# CentralUnit_Schematic.net
KiCad netlist of a schematic drawn in Altium Designer
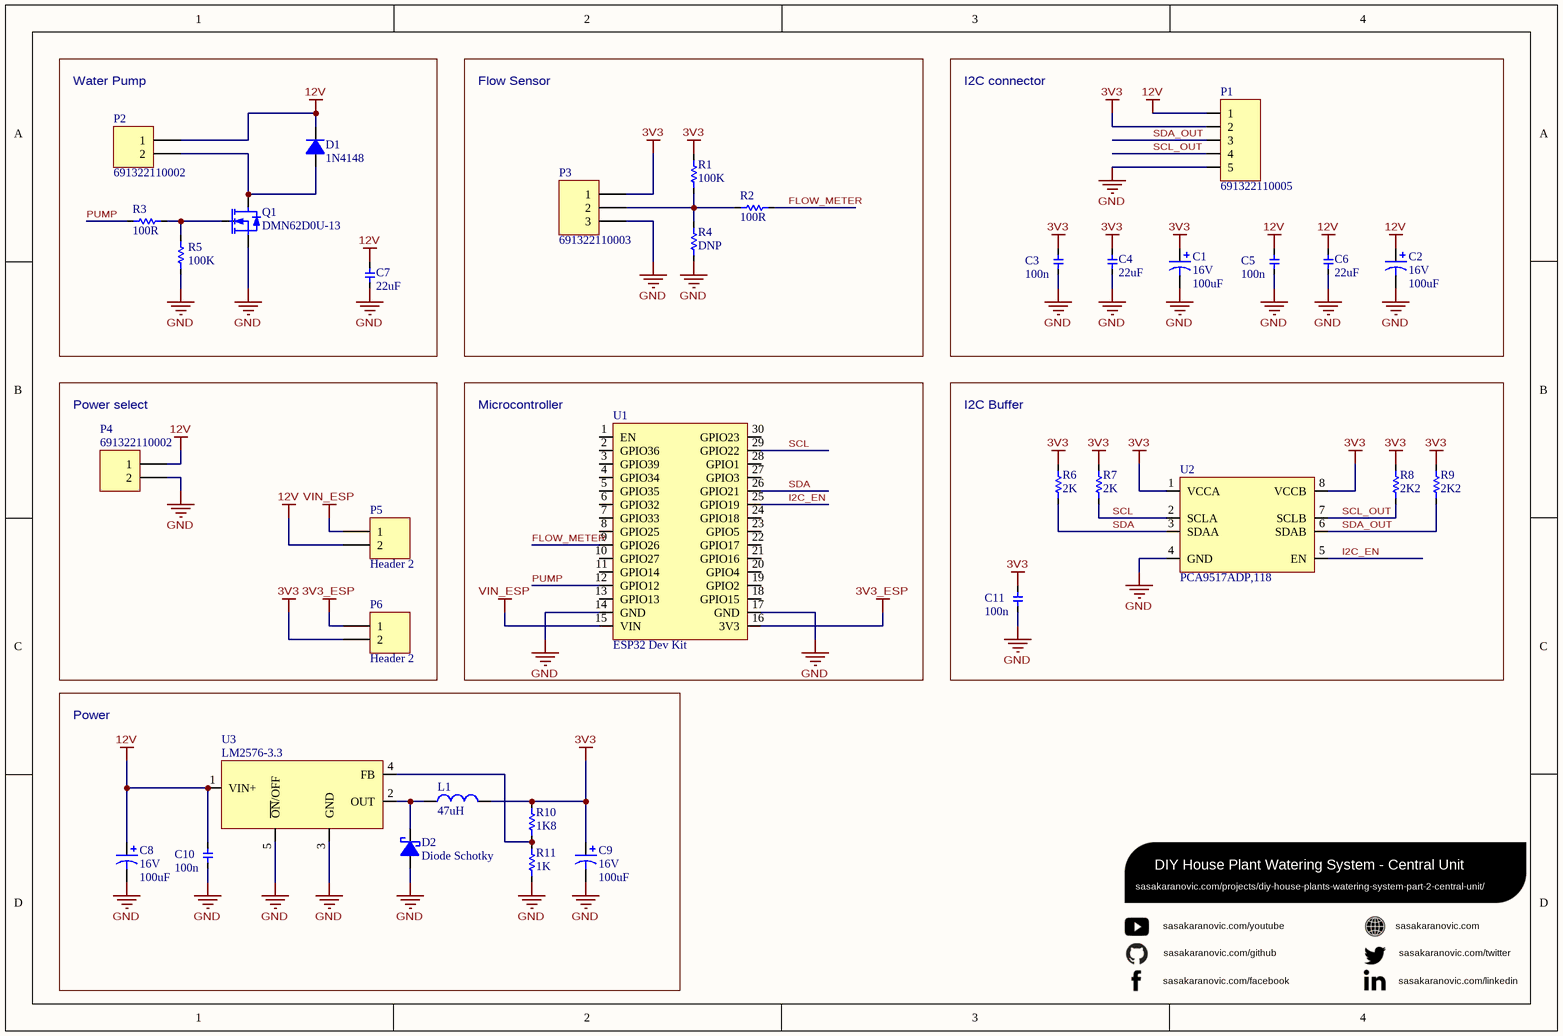
[diagram p0: CentralUnit_Schematic.SchDoc]

(export (version "E")
  (design (tool "Eeschema 10.0.6"))
  (components
    (comp (ref "C1")
      (value "16V")
      (footprint "Footprint_Misc:Electrolytic Cap 2.54mm")
      (description "Polarized Capacitor (Axial)")
      (fields
        (field (name "MANUFACTURER") "Nichicon")
        (field (name "MANUFACTURER PART NUMBER") "UKT1V101MED1TD")
        (field (name "ALTIUM_VALUE") "100uF")
      )
      (libsource (lib "Schematic_Misc") (part "Cap Electrolytic"))
    )
    (comp (ref "C2")
      (value "16V")
      (footprint "Footprint_Misc:Electrolytic Cap 2.54mm")
      (description "Polarized Capacitor (Axial)")
      (fields
        (field (name "MANUFACTURER") "Nichicon")
        (field (name "MANUFACTURER PART NUMBER") "UKT1V101MED1TD")
        (field (name "ALTIUM_VALUE") "100uF")
      )
      (libsource (lib "Schematic_Misc") (part "Cap Electrolytic"))
    )
    (comp (ref "C3")
      (value "100n")
      (footprint "Footprint_Misc:0603 - CAP HS")
      (description "CAP CER 0.1UF 50V X7R 0603")
      (fields
        (field (name "MANUFACTURER") "Samsung Electro-Mechanics")
        (field (name "MANUFACTURER PART NUMBER") "CL10B104KB8NNNL")
      )
      (libsource (lib "Moji Schematici") (part "Cap"))
    )
    (comp (ref "C4")
      (value "22uF")
      (footprint "Footprint_Misc:0603 - CAP HS")
      (description "Capacitor")
      (fields
        (field (name "MANUFACTURER") "Nichicon")
        (field (name "MANUFACTURER PART NUMBER") "UVZ1J220MDD1TD")
      )
      (libsource (lib "Moji Schematici") (part "Cap"))
    )
    (comp (ref "C5")
      (value "100n")
      (footprint "Footprint_Misc:0603 - CAP HS")
      (description "CAP CER 0.1UF 50V X7R 0603")
      (fields
        (field (name "MANUFACTURER") "Samsung Electro-Mechanics")
        (field (name "MANUFACTURER PART NUMBER") "CL10B104KB8NNNL")
      )
      (libsource (lib "Moji Schematici") (part "Cap"))
    )
    (comp (ref "C6")
      (value "22uF")
      (footprint "Footprint_Misc:0603 - CAP HS")
      (description "Capacitor")
      (fields
        (field (name "MANUFACTURER") "Nichicon")
        (field (name "MANUFACTURER PART NUMBER") "UVZ1J220MDD1TD")
      )
      (libsource (lib "Moji Schematici") (part "Cap"))
    )
    (comp (ref "C7")
      (value "22uF")
      (footprint "Footprint_Misc:0603 - CAP HS")
      (description "Capacitor")
      (fields
        (field (name "MANUFACTURER") "Nichicon")
        (field (name "MANUFACTURER PART NUMBER") "UVZ1J220MDD1TD")
      )
      (libsource (lib "Moji Schematici") (part "Cap"))
    )
    (comp (ref "C8")
      (value "16V")
      (footprint "Footprint_Misc:Electrolytic Cap 2.54mm")
      (description "Polarized Capacitor (Axial)")
      (fields
        (field (name "MANUFACTURER") "Nichicon")
        (field (name "MANUFACTURER PART NUMBER") "UKT1V101MED1TD")
        (field (name "ALTIUM_VALUE") "100uF")
      )
      (libsource (lib "Schematic_Misc") (part "Cap Electrolytic"))
    )
    (comp (ref "C9")
      (value "16V")
      (footprint "Footprint_Misc:Electrolytic Cap 2.54mm")
      (description "Polarized Capacitor (Axial)")
      (fields
        (field (name "MANUFACTURER") "Nichicon")
        (field (name "MANUFACTURER PART NUMBER") "UKT1V101MED1TD")
        (field (name "ALTIUM_VALUE") "100uF")
      )
      (libsource (lib "Schematic_Misc") (part "Cap Electrolytic"))
    )
    (comp (ref "C10")
      (value "100n")
      (footprint "Footprint_Misc:0603 - CAP HS")
      (description "CAP CER 0.1UF 50V X7R 0603")
      (fields
        (field (name "MANUFACTURER") "Samsung Electro-Mechanics")
        (field (name "MANUFACTURER PART NUMBER") "CL10B104KB8NNNL")
      )
      (libsource (lib "Moji Schematici") (part "Cap"))
    )
    (comp (ref "C11")
      (value "100n")
      (footprint "Footprint_Misc:0603 - CAP HS")
      (description "CAP CER 0.1UF 50V X7R 0603")
      (fields
        (field (name "MANUFACTURER") "Samsung Electro-Mechanics")
        (field (name "MANUFACTURER PART NUMBER") "CL10B104KB8NNNL")
      )
      (libsource (lib "Moji Schematici") (part "Cap"))
    )
    (comp (ref "D1")
      (value "1N4148")
      (footprint "Footprint_Misc:SOD123F")
      (description "DIODE GEN PURP 100V 300MA SOD123")
      (fields
        (field (name "DISTRIBUTOR PART NUMBER") "1N4148W-FDICT-ND")
        (field (name "MANUFACTURER") "Diodes Incorporated")
      )
      (libsource (lib "Moji Schematici (1)") (part "Diode"))
    )
    (comp (ref "D2")
      (value "Diode Schotky")
      (footprint "1206 Polarized")
      (fields
        (field (name "MANUFACTURER") "AVX Corporation")
        (field (name "MANUFACTURER PART NUMBER") "SD1206S040S1R0")
        (field (name "DISTRIBUTOR PART NUMBER") "478-7805-1-ND")
      )
      (libsource (lib "Schematic_Misc") (part "Diode Schotky"))
    )
    (comp (ref "L1")
      (value "47uH")
      (footprint "Footprint_Misc:IND_TH_SMD")
      (description "Shielded - Inductor 200mOhm Nonstandard")
      (fields
        (field (name "MANUFACTURER") "Laird-Signal Integrity Products")
        (field (name "MANUFACTURER PART NUMBER") "TYS6045470M-10")
      )
      (libsource (lib "Schematic_Misc") (part "Inductor"))
    )
    (comp (ref "P1")
      (value "691322110005")
      (footprint "Footprint_Misc:TERMINAL_5POS_90DEG_2PART")
      (description "TERM BLOCK HDR 5POS 90DEG 3.5MM")
      (fields
        (field (name "DISTRIBUTOR PART NUMBER") "732-2772-ND")
        (field (name "MANUFACTURER") "Würth Elektronik")
      )
      (libsource (lib "Schematic_Misc") (part "Terminal 5_691322110005"))
    )
    (comp (ref "P2")
      (value "691322110002")
      (footprint "Footprint_Misc:TERMINAL_2POS_90DEG_2PART")
      (fields
        (field (name "MANUFACTURER") "Würth Elektronik")
        (field (name "DISTRIBUTOR PART NUMBER") "732-2769-ND")
      )
      (libsource (lib "Schematic_Misc") (part "Terminal 2_691322110002"))
    )
    (comp (ref "P3")
      (value "691322110003")
      (footprint "Footprint_Misc:TERMINAL_3POS_90DEG_2PART")
      (description "TERM BLOCK HDR 3POS 90DEG 3.5MM")
      (fields
        (field (name "MANUFACTURER") "Würth Elektronik")
        (field (name "DISTRIBUTOR PART NUMBER") "732-2770-ND")
      )
      (libsource (lib "Schematic_Misc") (part "Terminal 3_691322110003_1"))
    )
    (comp (ref "P4")
      (value "691322110002")
      (footprint "Footprint_Misc:TERMINAL_2POS_90DEG_2PART")
      (fields
        (field (name "MANUFACTURER") "Würth Elektronik")
        (field (name "DISTRIBUTOR PART NUMBER") "732-2769-ND")
      )
      (libsource (lib "Schematic_Misc") (part "Terminal 2_691322110002"))
    )
    (comp (ref "P5")
      (value "Header 2")
      (footprint "Footprint_Misc:Header 2x1")
      (description "Header, 2-Pin")
      (fields
        (field (name "DISTRIBUTOR PART NUMBER") "952-2244-ND")
        (field (name "MANUFACTURER") "Harwin Inc.")
      )
      (libsource (lib "Schematic_Misc") (part "Header 2"))
    )
    (comp (ref "P6")
      (value "Header 2")
      (footprint "Footprint_Misc:Header 2x1")
      (description "Header, 2-Pin")
      (fields
        (field (name "DISTRIBUTOR PART NUMBER") "952-2244-ND")
        (field (name "MANUFACTURER") "Harwin Inc.")
      )
      (libsource (lib "Schematic_Misc") (part "Header 2"))
    )
    (comp (ref "Q1")
      (value "DMN62D0U-13")
      (footprint "Footprint_Misc:SOT90P240X100-3N")
      (description "MOSFET N-CH 60V 0.38A")
      (fields
        (field (name "MANUFACTURER") "Diodes Incorporated")
        (field (name "DISTRIBUTOR PART NUMBER") "DMN62D0U-13DICT-ND")
      )
      (libsource (lib "Schematic_Misc") (part "DMN62D0U-13"))
    )
    (comp (ref "R1")
      (value "100K")
      (footprint "Footprint_Misc:0603 - HS")
      (description "RES SMD 0 OHM JUMPER 1/10W 0603")
      (fields (field (name "DISTRIBUTOR PART NUMBER") "311-0.0LECT-ND") (field (name "MANUFACTURER") "Yageo"))
      (libsource (lib "Moji Schematici") (part "Res"))
    )
    (comp (ref "R2")
      (value "100R")
      (footprint "Footprint_Misc:0603 - HS")
      (description "RES SMD 0 OHM JUMPER 1/10W 0603")
      (fields (field (name "DISTRIBUTOR PART NUMBER") "311-0.0LECT-ND") (field (name "MANUFACTURER") "Yageo"))
      (libsource (lib "Moji Schematici") (part "Res"))
    )
    (comp (ref "R3")
      (value "100R")
      (footprint "Footprint_Misc:0603 - HS")
      (description "RES SMD 0 OHM JUMPER 1/10W 0603")
      (fields (field (name "DISTRIBUTOR PART NUMBER") "311-0.0LECT-ND") (field (name "MANUFACTURER") "Yageo"))
      (libsource (lib "Moji Schematici") (part "Res"))
    )
    (comp (ref "R4")
      (value "DNP")
      (footprint "Footprint_Misc:0603 - HS")
      (description "RES SMD 0 OHM JUMPER 1/10W 0603")
      (fields (field (name "DISTRIBUTOR PART NUMBER") "311-0.0LECT-ND") (field (name "MANUFACTURER") "Yageo"))
      (libsource (lib "Moji Schematici") (part "Res"))
    )
    (comp (ref "R5")
      (value "100K")
      (footprint "Footprint_Misc:0603 - HS")
      (description "RES SMD 1M OHM 5% 1/10W 0603")
      (fields
        (field (name "DISTRIBUTOR PART NUMBER") "311-1.0MGRCT-ND")
        (field (name "MANUFACTURER") "Yageo")
      )
      (libsource (lib "Moji Schematici") (part "Res"))
    )
    (comp (ref "R6")
      (value "2K")
      (footprint "Footprint_Misc:0603 - HS")
      (description "RES SMD 0 OHM JUMPER 1/10W 0603")
      (fields (field (name "DISTRIBUTOR PART NUMBER") "311-0.0LECT-ND") (field (name "MANUFACTURER") "Yageo"))
      (libsource (lib "Moji Schematici") (part "Res"))
    )
    (comp (ref "R7")
      (value "2K")
      (footprint "Footprint_Misc:0603 - HS")
      (description "RES SMD 0 OHM JUMPER 1/10W 0603")
      (fields (field (name "DISTRIBUTOR PART NUMBER") "311-0.0LECT-ND") (field (name "MANUFACTURER") "Yageo"))
      (libsource (lib "Moji Schematici") (part "Res"))
    )
    (comp (ref "R8")
      (value "2K2")
      (footprint "Footprint_Misc:0603 - HS")
      (description "RES SMD 0 OHM JUMPER 1/10W 0603")
      (fields (field (name "DISTRIBUTOR PART NUMBER") "311-0.0LECT-ND") (field (name "MANUFACTURER") "Yageo"))
      (libsource (lib "Moji Schematici") (part "Res"))
    )
    (comp (ref "R9")
      (value "2K2")
      (footprint "Footprint_Misc:0603 - HS")
      (description "RES SMD 0 OHM JUMPER 1/10W 0603")
      (fields (field (name "DISTRIBUTOR PART NUMBER") "311-0.0LECT-ND") (field (name "MANUFACTURER") "Yageo"))
      (libsource (lib "Moji Schematici") (part "Res"))
    )
    (comp (ref "R10")
      (value "1K8")
      (footprint "Footprint_Misc:0603 - HS")
      (description "Resistor")
      (fields
        (field (name "DISTRIBUTOR PART NUMBER") "311-1.8KGRCT-ND")
        (field (name "MANUFACTURER") "Yageo")
      )
      (libsource (lib "Schematic_Misc") (part "Res"))
    )
    (comp (ref "R11")
      (value "1K")
      (footprint "Footprint_Misc:0603 - HS")
      (description "Resistor")
      (fields
        (field (name "DISTRIBUTOR PART NUMBER") "311-1.0KGRCT-ND")
        (field (name "MANUFACTURER") "Yageo")
      )
      (libsource (lib "Schematic_Misc") (part "Res"))
    )
    (comp (ref "U1")
      (value "ESP32 Dev Kit")
      (footprint "Footprint_Misc:ESP32-DevModule")
      (fields
        (field (name "DISTRIBUTOR PART NUMBER") "TBD")
        (field (name "MANUFACTURER") "Espressif")
        (field (name "MANUFACTURER PART NUMBER") "ESP32-Dev Module")
      )
      (libsource (lib "Schematic_Misc") (part "ESP32_DEV"))
    )
    (comp (ref "U2")
      (value "PCA9517ADP,118")
      (footprint "Footprint_Misc:MSOP8-3mm")
      (description "IC REDRIVER I2C 1CH 8TSSOP")
      (fields
        (field (name "MANUFACTURER") "NXP USA Inc.")
        (field (name "DISTRIBUTOR PART NUMBER") "568-5926-1-ND")
      )
      (libsource (lib "Schematic_Misc") (part "PCA9517ADP,118"))
    )
    (comp (ref "U3")
      (value "LM2576-3.3")
      (footprint "Footprint_Misc:TO263-5")
      (fields
        (field (name "MANUFACTURER") "Texas Instruments")
        (field (name "MANUFACTURER PART NUMBER") "LM2596S-3.3/NOPB")
        (field (name "DISTRIBUTOR PART NUMBER") "LM2596S-3.3/NOPB-ND")
      )
      (libsource (lib "Schematic_Misc") (part "LM2576-xx"))
    )
  )
  (nets
    (net (code "1") (name "/FLOW_METER") (class "Default")
      (node (ref "R2") (pin "2") (pinfunction "2_2") (pintype "passive"))
      (node (ref "U1") (pin "9") (pinfunction "GPIO26_9") (pintype "passive"))
    )
    (net (code "2") (name "/I2C_EN") (class "Default")
      (node (ref "U1") (pin "25") (pinfunction "GPIO19_25") (pintype "passive"))
      (node (ref "U2") (pin "5") (pinfunction "EN_5") (pintype "passive"))
    )
    (net (code "3") (name "/PUMP") (class "Default")
      (node (ref "R3") (pin "1") (pinfunction "1_1") (pintype "passive"))
      (node (ref "U1") (pin "12") (pinfunction "GPIO12_12") (pintype "passive"))
    )
    (net (code "4") (name "/SCL") (class "Default")
      (node (ref "R7") (pin "1") (pinfunction "1_1") (pintype "passive"))
      (node (ref "U1") (pin "29") (pinfunction "GPIO22_29") (pintype "passive"))
      (node (ref "U2") (pin "2") (pinfunction "SCLA_2") (pintype "passive"))
    )
    (net (code "5") (name "/SCL_OUT") (class "Default")
      (node (ref "P1") (pin "4") (pinfunction "4_4") (pintype "passive"))
      (node (ref "R8") (pin "1") (pinfunction "1_1") (pintype "passive"))
      (node (ref "U2") (pin "7") (pinfunction "SCLB_7") (pintype "passive"))
    )
    (net (code "6") (name "/SDA") (class "Default")
      (node (ref "R6") (pin "1") (pinfunction "1_1") (pintype "passive"))
      (node (ref "U1") (pin "26") (pinfunction "GPIO21_26") (pintype "passive"))
      (node (ref "U2") (pin "3") (pinfunction "SDAA_3") (pintype "passive"))
    )
    (net (code "7") (name "/SDA_OUT") (class "Default")
      (node (ref "P1") (pin "3") (pinfunction "3_3") (pintype "passive"))
      (node (ref "R9") (pin "1") (pinfunction "1_1") (pintype "passive"))
      (node (ref "U2") (pin "6") (pinfunction "SDAB_6") (pintype "passive"))
    )
    (net (code "8") (name "3V3") (class "Default")
      (node (ref "C1") (pin "1") (pinfunction "1_1") (pintype "passive"))
      (node (ref "C11") (pin "2") (pinfunction "2_2") (pintype "passive"))
      (node (ref "C3") (pin "2") (pinfunction "2_2") (pintype "passive"))
      (node (ref "C4") (pin "2") (pinfunction "2_2") (pintype "passive"))
      (node (ref "C9") (pin "1") (pinfunction "1_1") (pintype "passive"))
      (node (ref "L1") (pin "2") (pinfunction "2_2") (pintype "passive"))
      (node (ref "P1") (pin "2") (pinfunction "2_2") (pintype "passive"))
      (node (ref "P3") (pin "1") (pinfunction "1_1") (pintype "passive"))
      (node (ref "P6") (pin "2") (pinfunction "2_2") (pintype "passive"))
      (node (ref "R1") (pin "2") (pinfunction "2_2") (pintype "passive"))
      (node (ref "R10") (pin "1") (pinfunction "1_1") (pintype "passive"))
      (node (ref "R6") (pin "2") (pinfunction "2_2") (pintype "passive"))
      (node (ref "R7") (pin "2") (pinfunction "2_2") (pintype "passive"))
      (node (ref "R8") (pin "2") (pinfunction "2_2") (pintype "passive"))
      (node (ref "R9") (pin "2") (pinfunction "2_2") (pintype "passive"))
      (node (ref "U2") (pin "1") (pinfunction "VCCA_1") (pintype "passive"))
      (node (ref "U2") (pin "8") (pinfunction "VCCB_8") (pintype "passive"))
    )
    (net (code "9") (name "3V3_ESP") (class "Default")
      (node (ref "P6") (pin "1") (pinfunction "1_1") (pintype "passive"))
      (node (ref "U1") (pin "16") (pinfunction "3V3_16") (pintype "passive"))
    )
    (net (code "10") (name "12V") (class "Default")
      (node (ref "C10") (pin "2") (pinfunction "2_2") (pintype "passive"))
      (node (ref "C2") (pin "1") (pinfunction "1_1") (pintype "passive"))
      (node (ref "C5") (pin "2") (pinfunction "2_2") (pintype "passive"))
      (node (ref "C6") (pin "2") (pinfunction "2_2") (pintype "passive"))
      (node (ref "C7") (pin "2") (pinfunction "2_2") (pintype "passive"))
      (node (ref "C8") (pin "1") (pinfunction "1_1") (pintype "passive"))
      (node (ref "D1") (pin "K") (pinfunction "K_K") (pintype "passive"))
      (node (ref "P1") (pin "1") (pinfunction "1_1") (pintype "passive"))
      (node (ref "P2") (pin "1") (pinfunction "1_1") (pintype "passive"))
      (node (ref "P4") (pin "1") (pinfunction "1_1") (pintype "passive"))
      (node (ref "P5") (pin "2") (pinfunction "2_2") (pintype "passive"))
      (node (ref "U3") (pin "1") (pinfunction "VIN+_1") (pintype "passive"))
    )
    (net (code "11") (name "GND") (class "Default")
      (node (ref "C1") (pin "2") (pinfunction "2_2") (pintype "passive"))
      (node (ref "C10") (pin "1") (pinfunction "1_1") (pintype "passive"))
      (node (ref "C11") (pin "1") (pinfunction "1_1") (pintype "passive"))
      (node (ref "C2") (pin "2") (pinfunction "2_2") (pintype "passive"))
      (node (ref "C3") (pin "1") (pinfunction "1_1") (pintype "passive"))
      (node (ref "C4") (pin "1") (pinfunction "1_1") (pintype "passive"))
      (node (ref "C5") (pin "1") (pinfunction "1_1") (pintype "passive"))
      (node (ref "C6") (pin "1") (pinfunction "1_1") (pintype "passive"))
      (node (ref "C7") (pin "1") (pinfunction "1_1") (pintype "passive"))
      (node (ref "C8") (pin "2") (pinfunction "2_2") (pintype "passive"))
      (node (ref "C9") (pin "2") (pinfunction "2_2") (pintype "passive"))
      (node (ref "D2") (pin "A") (pinfunction "A_A") (pintype "passive"))
      (node (ref "P1") (pin "5") (pinfunction "5_5") (pintype "passive"))
      (node (ref "P3") (pin "3") (pinfunction "3_3") (pintype "passive"))
      (node (ref "P4") (pin "2") (pinfunction "2_2") (pintype "passive"))
      (node (ref "Q1") (pin "2") (pinfunction "S_2") (pintype "passive"))
      (node (ref "R11") (pin "2") (pinfunction "2_2") (pintype "passive"))
      (node (ref "R4") (pin "1") (pinfunction "1_1") (pintype "passive"))
      (node (ref "R5") (pin "1") (pinfunction "1_1") (pintype "passive"))
      (node (ref "U1") (pin "14") (pinfunction "GND_14") (pintype "passive"))
      (node (ref "U1") (pin "17") (pinfunction "GND_17") (pintype "passive"))
      (node (ref "U2") (pin "4") (pinfunction "GND_4") (pintype "passive"))
      (node (ref "U3") (pin "3") (pinfunction "GND_3") (pintype "passive"))
      (node (ref "U3") (pin "5") (pinfunction "~{ON}/OFF_5") (pintype "passive"))
    )
    (net (code "12") (name "Net-(P3-Pad2)") (class "Default")
      (node (ref "P3") (pin "2") (pinfunction "2_2") (pintype "passive"))
      (node (ref "R1") (pin "1") (pinfunction "1_1") (pintype "passive"))
      (node (ref "R2") (pin "1") (pinfunction "1_1") (pintype "passive"))
      (node (ref "R4") (pin "2") (pinfunction "2_2") (pintype "passive"))
    )
    (net (code "13") (name "Net-(Q1-D)") (class "Default")
      (node (ref "D1") (pin "A") (pinfunction "A_A") (pintype "passive"))
      (node (ref "P2") (pin "2") (pinfunction "2_2") (pintype "passive"))
      (node (ref "Q1") (pin "3") (pinfunction "D_3") (pintype "passive"))
    )
    (net (code "14") (name "Net-(Q1-G)") (class "Default")
      (node (ref "Q1") (pin "1") (pinfunction "G_1") (pintype "passive"))
      (node (ref "R3") (pin "2") (pinfunction "2_2") (pintype "passive"))
      (node (ref "R5") (pin "2") (pinfunction "2_2") (pintype "passive"))
    )
    (net (code "15") (name "Net-(U3-FB)") (class "Default")
      (node (ref "R10") (pin "2") (pinfunction "2_2") (pintype "passive"))
      (node (ref "R11") (pin "1") (pinfunction "1_1") (pintype "passive"))
      (node (ref "U3") (pin "4") (pinfunction "FB_4") (pintype "passive"))
    )
    (net (code "16") (name "Net-(U3-OUT)") (class "Default")
      (node (ref "D2") (pin "K") (pinfunction "K_K") (pintype "passive"))
      (node (ref "L1") (pin "1") (pinfunction "1_1") (pintype "passive"))
      (node (ref "U3") (pin "2") (pinfunction "OUT_2") (pintype "passive"))
    )
    (net (code "17") (name "VIN_ESP") (class "Default")
      (node (ref "P5") (pin "1") (pinfunction "1_1") (pintype "passive"))
      (node (ref "U1") (pin "15") (pinfunction "VIN_15") (pintype "passive"))
    )
    (net (code "18") (name "unconnected-(U1-EN-Pad1)") (class "Default")
      (node (ref "U1") (pin "1") (pinfunction "EN_1") (pintype "passive"))
    )
    (net (code "19") (name "unconnected-(U1-GPIO1-Pad28)") (class "Default")
      (node (ref "U1") (pin "28") (pinfunction "GPIO1_28") (pintype "passive"))
    )
    (net (code "20") (name "unconnected-(U1-GPIO2-Pad19)") (class "Default")
      (node (ref "U1") (pin "19") (pinfunction "GPIO2_19") (pintype "passive"))
    )
    (net (code "21") (name "unconnected-(U1-GPIO3-Pad27)") (class "Default")
      (node (ref "U1") (pin "27") (pinfunction "GPIO3_27") (pintype "passive"))
    )
    (net (code "22") (name "unconnected-(U1-GPIO4-Pad20)") (class "Default")
      (node (ref "U1") (pin "20") (pinfunction "GPIO4_20") (pintype "passive"))
    )
    (net (code "23") (name "unconnected-(U1-GPIO5-Pad23)") (class "Default")
      (node (ref "U1") (pin "23") (pinfunction "GPIO5_23") (pintype "passive"))
    )
    (net (code "24") (name "unconnected-(U1-GPIO13-Pad13)") (class "Default")
      (node (ref "U1") (pin "13") (pinfunction "GPIO13_13") (pintype "passive"))
    )
    (net (code "25") (name "unconnected-(U1-GPIO14-Pad11)") (class "Default")
      (node (ref "U1") (pin "11") (pinfunction "GPIO14_11") (pintype "passive"))
    )
    (net (code "26") (name "unconnected-(U1-GPIO15-Pad18)") (class "Default")
      (node (ref "U1") (pin "18") (pinfunction "GPIO15_18") (pintype "passive"))
    )
    (net (code "27") (name "unconnected-(U1-GPIO16-Pad21)") (class "Default")
      (node (ref "U1") (pin "21") (pinfunction "GPIO16_21") (pintype "passive"))
    )
    (net (code "28") (name "unconnected-(U1-GPIO17-Pad22)") (class "Default")
      (node (ref "U1") (pin "22") (pinfunction "GPIO17_22") (pintype "passive"))
    )
    (net (code "29") (name "unconnected-(U1-GPIO18-Pad24)") (class "Default")
      (node (ref "U1") (pin "24") (pinfunction "GPIO18_24") (pintype "passive"))
    )
    (net (code "30") (name "unconnected-(U1-GPIO23-Pad30)") (class "Default")
      (node (ref "U1") (pin "30") (pinfunction "GPIO23_30") (pintype "passive"))
    )
    (net (code "31") (name "unconnected-(U1-GPIO25-Pad8)") (class "Default")
      (node (ref "U1") (pin "8") (pinfunction "GPIO25_8") (pintype "passive"))
    )
    (net (code "32") (name "unconnected-(U1-GPIO27-Pad10)") (class "Default")
      (node (ref "U1") (pin "10") (pinfunction "GPIO27_10") (pintype "passive"))
    )
    (net (code "33") (name "unconnected-(U1-GPIO32-Pad6)") (class "Default")
      (node (ref "U1") (pin "6") (pinfunction "GPIO32_6") (pintype "passive"))
    )
    (net (code "34") (name "unconnected-(U1-GPIO33-Pad7)") (class "Default")
      (node (ref "U1") (pin "7") (pinfunction "GPIO33_7") (pintype "passive"))
    )
    (net (code "35") (name "unconnected-(U1-GPIO34-Pad4)") (class "Default")
      (node (ref "U1") (pin "4") (pinfunction "GPIO34_4") (pintype "passive"))
    )
    (net (code "36") (name "unconnected-(U1-GPIO35-Pad5)") (class "Default")
      (node (ref "U1") (pin "5") (pinfunction "GPIO35_5") (pintype "passive"))
    )
    (net (code "37") (name "unconnected-(U1-GPIO36-Pad2)") (class "Default")
      (node (ref "U1") (pin "2") (pinfunction "GPIO36_2") (pintype "passive"))
    )
    (net (code "38") (name "unconnected-(U1-GPIO39-Pad3)") (class "Default")
      (node (ref "U1") (pin "3") (pinfunction "GPIO39_3") (pintype "passive"))
    )
  )
)
